# 5_RF.net
KiCad netlist of a schematic drawn in Altium Designer
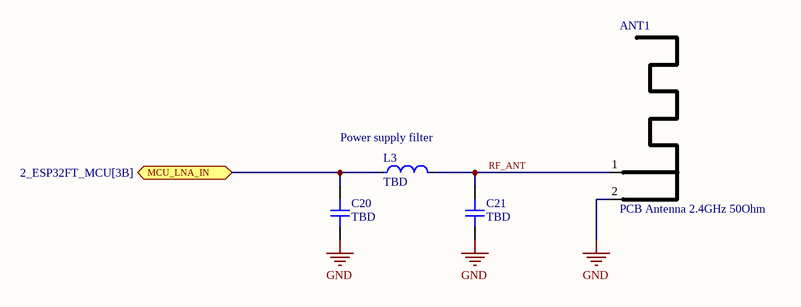
[diagram p0: 5_RF.SchDoc]

(export (version "E")
  (design (tool "Eeschema 10.0.6"))
  (components
    (comp (ref "ANT1")
      (value "PCB Antenna 2.4GHz 50Ohm")
      (footprint "ANT_IFA_USB_2_4GHZ_50R")
      (description "Inverted F 2.4GHz ISM PCB Antenna 50 Ohm")
      (libsource (lib "Schematic-Lib-PhilsLab") (part "ANT_IFA_USB_2_4GHZ_50R"))
    )
    (comp (ref "C20")
      (value "TBD")
      (footprint "CAP_0402")
      (description "Capacitor SMD 0402 16V")
      (libsource (lib "Schematic-Lib-PhilsLab") (part "CAP_0402_16V"))
    )
    (comp (ref "C21")
      (value "TBD")
      (footprint "CAP_0402")
      (description "Capacitor SMD 0402 16V")
      (libsource (lib "Schematic-Lib-PhilsLab") (part "CAP_0402_16V"))
    )
    (comp (ref "L3")
      (value "TBD")
      (footprint "FP-LQW15AN_80-MFG")
      (description "Wire Wound RF Inductor 2.2nH ±2% 2530mA 0.022Ω 0402 (1005)")
      (libsource (lib "Altium Content Vault") (part "725321dda6339637d4d059423bc1c3c"))
    )
  )
  (nets
    (net (code "1") (name "/MCU_LNA_IN") (class "Default")
      (node (ref "C20") (pin "2") (pinfunction "2_2") (pintype "passive"))
      (node (ref "L3") (pin "1") (pinfunction "1_1") (pintype "passive"))
    )
    (net (code "2") (name "/RF_ANT") (class "Default")
      (node (ref "ANT1") (pin "1") (pinfunction "RF_1") (pintype "passive"))
      (node (ref "C21") (pin "2") (pinfunction "2_2") (pintype "passive"))
      (node (ref "L3") (pin "2") (pinfunction "2_2") (pintype "passive"))
    )
    (net (code "3") (name "GND") (class "Default")
      (node (ref "ANT1") (pin "2") (pinfunction "GND_2") (pintype "passive"))
      (node (ref "C20") (pin "1") (pinfunction "1_1") (pintype "passive"))
      (node (ref "C21") (pin "1") (pinfunction "1_1") (pintype "passive"))
    )
  )
)
